# preamp.net
KiCad netlist of a schematic drawn in Altium Designer
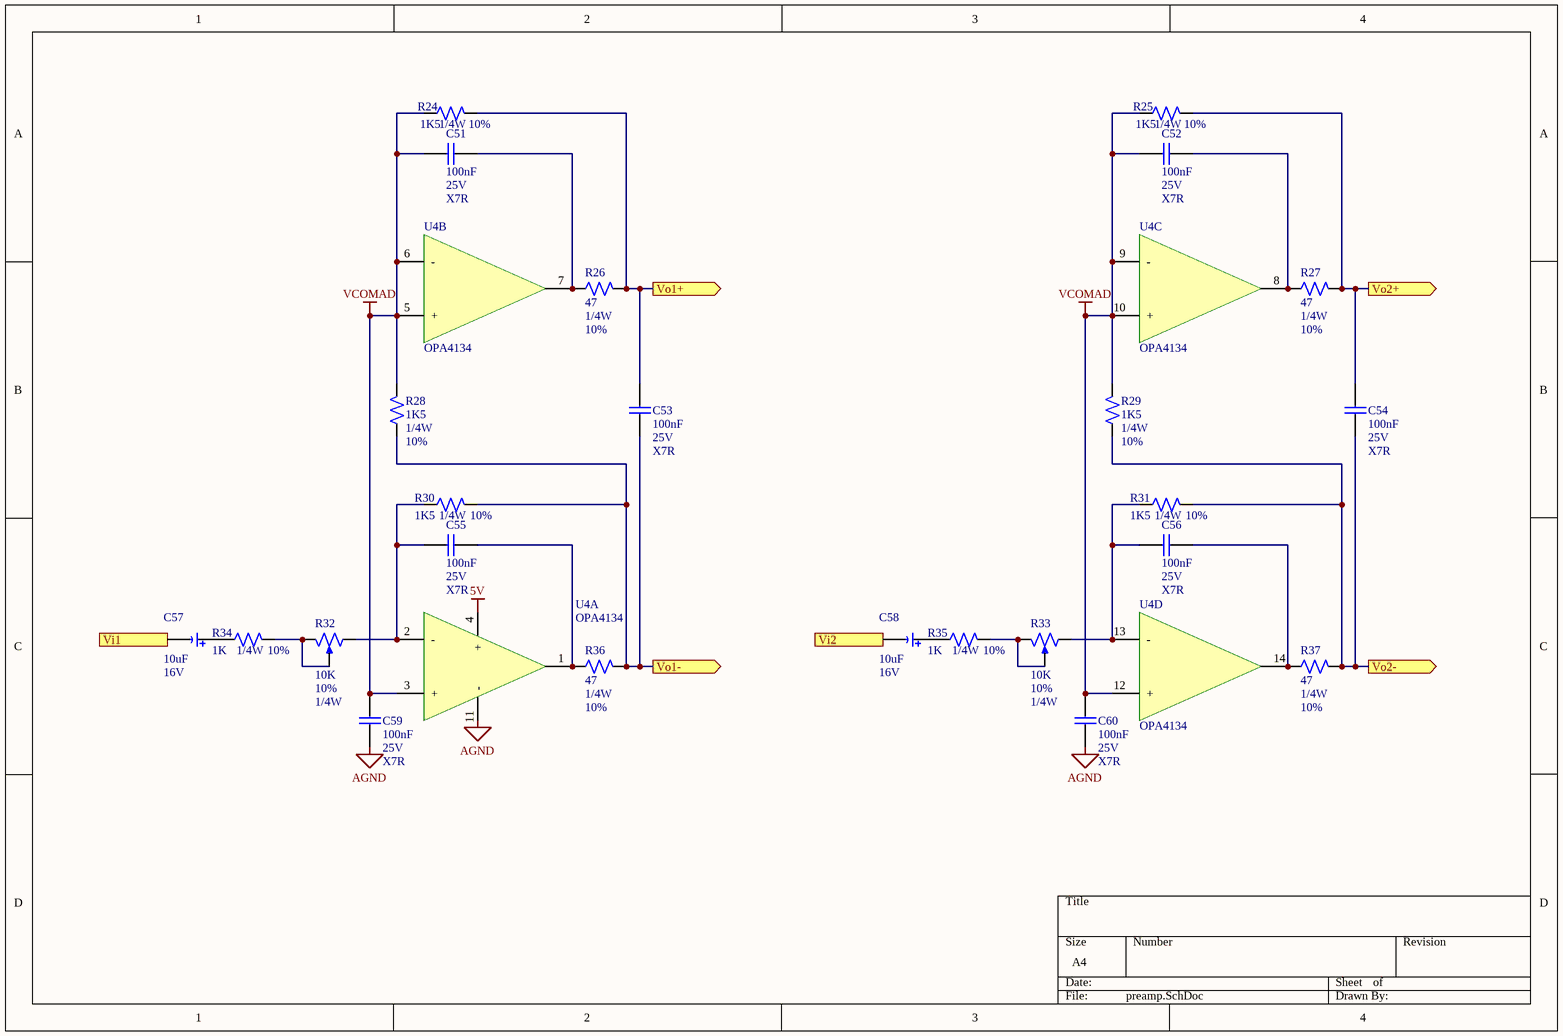
[diagram p0: preamp.SchDoc]

(export (version "E")
  (design (tool "Eeschema 10.0.6"))
  (components
    (comp (ref "C51")
      (value "Capacitor")
      (footprint "C0805")
      (description "Capacitor de placas paralelas")
      (fields (field (name "VALOR") "100nF") (field (name "TENSION") "25V") (field (name "TOLERANCIA") "X7R"))
      (libsource (lib "Sch_Comunes") (part "Capacitor"))
    )
    (comp (ref "C52")
      (value "Capacitor")
      (footprint "C0805")
      (description "Capacitor de placas paralelas")
      (fields (field (name "VALOR") "100nF") (field (name "TENSION") "25V") (field (name "TOLERANCIA") "X7R"))
      (libsource (lib "Sch_Comunes") (part "Capacitor"))
    )
    (comp (ref "C53")
      (value "Capacitor")
      (footprint "C0805")
      (description "Capacitor de placas paralelas")
      (fields (field (name "VALOR") "100nF") (field (name "TENSION") "25V") (field (name "TOLERANCIA") "X7R"))
      (libsource (lib "Sch_Comunes") (part "Capacitor"))
    )
    (comp (ref "C54")
      (value "Capacitor")
      (footprint "C0805")
      (description "Capacitor de placas paralelas")
      (fields (field (name "VALOR") "100nF") (field (name "TENSION") "25V") (field (name "TOLERANCIA") "X7R"))
      (libsource (lib "Sch_Comunes") (part "Capacitor"))
    )
    (comp (ref "C55")
      (value "Capacitor")
      (footprint "C0805")
      (description "Capacitor de placas paralelas")
      (fields (field (name "VALOR") "100nF") (field (name "TENSION") "25V") (field (name "TOLERANCIA") "X7R"))
      (libsource (lib "Sch_Comunes") (part "Capacitor"))
    )
    (comp (ref "C56")
      (value "Capacitor")
      (footprint "C0805")
      (description "Capacitor de placas paralelas")
      (fields (field (name "VALOR") "100nF") (field (name "TENSION") "25V") (field (name "TOLERANCIA") "X7R"))
      (libsource (lib "Sch_Comunes") (part "Capacitor"))
    )
    (comp (ref "C57")
      (value "Capacitor polarizado")
      (footprint "CAP_Electrolytic")
      (fields (field (name "VALOR") "10uF") (field (name "TENSION") "16V"))
      (libsource (lib "sch_comunes") (part "Capacitor polarizado"))
    )
    (comp (ref "C58")
      (value "Capacitor polarizado")
      (footprint "CAP_Electrolytic")
      (fields (field (name "VALOR") "10uF") (field (name "TENSION") "16V"))
      (libsource (lib "sch_comunes") (part "Capacitor polarizado"))
    )
    (comp (ref "C59")
      (value "Capacitor")
      (footprint "C0805")
      (description "Capacitor de placas paralelas")
      (fields (field (name "VALOR") "100nF") (field (name "TENSION") "25V") (field (name "TOLERANCIA") "X7R"))
      (libsource (lib "Sch_Comunes") (part "Capacitor"))
    )
    (comp (ref "C60")
      (value "Capacitor")
      (footprint "C0805")
      (description "Capacitor de placas paralelas")
      (fields (field (name "VALOR") "100nF") (field (name "TENSION") "25V") (field (name "TOLERANCIA") "X7R"))
      (libsource (lib "Sch_Comunes") (part "Capacitor"))
    )
    (comp (ref "R24")
      (value "Resistor")
      (footprint "R0805")
      (description "Resistencia")
      (fields (field (name "VALOR") "1K5") (field (name "POTENCIA") "1/4W") (field (name "TOLERANCIA") "10%"))
      (libsource (lib "sch_comunes") (part "Resistor"))
    )
    (comp (ref "R25")
      (value "Resistor")
      (footprint "R0805")
      (description "Resistencia")
      (fields (field (name "VALOR") "1K5") (field (name "POTENCIA") "1/4W") (field (name "TOLERANCIA") "10%"))
      (libsource (lib "sch_comunes") (part "Resistor"))
    )
    (comp (ref "R26")
      (value "Resistor")
      (footprint "R0805")
      (description "Resistencia")
      (fields (field (name "VALOR") "47") (field (name "POTENCIA") "1/4W") (field (name "TOLERANCIA") "10%"))
      (libsource (lib "sch_comunes") (part "Resistor"))
    )
    (comp (ref "R27")
      (value "Resistor")
      (footprint "R0805")
      (description "Resistencia")
      (fields (field (name "VALOR") "47") (field (name "POTENCIA") "1/4W") (field (name "TOLERANCIA") "10%"))
      (libsource (lib "sch_comunes") (part "Resistor"))
    )
    (comp (ref "R28")
      (value "Resistor")
      (footprint "R0805")
      (description "Resistencia")
      (fields (field (name "VALOR") "1K5") (field (name "POTENCIA") "1/4W") (field (name "TOLERANCIA") "10%"))
      (libsource (lib "sch_comunes") (part "Resistor"))
    )
    (comp (ref "R29")
      (value "Resistor")
      (footprint "R0805")
      (description "Resistencia")
      (fields (field (name "VALOR") "1K5") (field (name "POTENCIA") "1/4W") (field (name "TOLERANCIA") "10%"))
      (libsource (lib "sch_comunes") (part "Resistor"))
    )
    (comp (ref "R30")
      (value "Resistor")
      (footprint "R0805")
      (description "Resistencia")
      (fields (field (name "VALOR") "1K5") (field (name "POTENCIA") "1/4W") (field (name "TOLERANCIA") "10%"))
      (libsource (lib "sch_comunes") (part "Resistor"))
    )
    (comp (ref "R31")
      (value "Resistor")
      (footprint "R0805")
      (description "Resistencia")
      (fields (field (name "VALOR") "1K5") (field (name "POTENCIA") "1/4W") (field (name "TOLERANCIA") "10%"))
      (libsource (lib "sch_comunes") (part "Resistor"))
    )
    (comp (ref "R32")
      (value "Potenciometro")
      (footprint "Header 3x1")
      (fields (field (name "VALOR") "10K") (field (name "TOLERANCIA") "10%") (field (name "POTENCIA") "1/4W"))
      (libsource (lib "sch_comunes") (part "Potenciometer"))
    )
    (comp (ref "R33")
      (value "Potenciometro")
      (footprint "Header 3x1")
      (fields (field (name "VALOR") "10K") (field (name "TOLERANCIA") "10%") (field (name "POTENCIA") "1/4W"))
      (libsource (lib "sch_comunes") (part "Potenciometer"))
    )
    (comp (ref "R34")
      (value "Resistor")
      (footprint "R0805")
      (description "Resistencia")
      (fields (field (name "VALOR") "1K") (field (name "POTENCIA") "1/4W") (field (name "TOLERANCIA") "10%"))
      (libsource (lib "sch_comunes") (part "Resistor"))
    )
    (comp (ref "R35")
      (value "Resistor")
      (footprint "R0805")
      (description "Resistencia")
      (fields (field (name "VALOR") "1K") (field (name "POTENCIA") "1/4W") (field (name "TOLERANCIA") "10%"))
      (libsource (lib "sch_comunes") (part "Resistor"))
    )
    (comp (ref "R36")
      (value "Resistor")
      (footprint "R0805")
      (description "Resistencia")
      (fields (field (name "VALOR") "47") (field (name "POTENCIA") "1/4W") (field (name "TOLERANCIA") "10%"))
      (libsource (lib "sch_comunes") (part "Resistor"))
    )
    (comp (ref "R37")
      (value "Resistor")
      (footprint "R0805")
      (description "Resistencia")
      (fields (field (name "VALOR") "47") (field (name "POTENCIA") "1/4W") (field (name "TOLERANCIA") "10%"))
      (libsource (lib "sch_comunes") (part "Resistor"))
    )
    (comp (ref "U4")
      (value "OPA4134")
      (footprint "TSSOP-14")
      (description "Integrado con 4 operacionales")
      (libsource (lib "sch_opamp") (part "Opamp_x4"))
    )
  )
  (nets
    (net (code "1") (name "/Vi1") (class "Default")
      (node (ref "C57") (pin "2") (pinfunction "2_2") (pintype "passive"))
    )
    (net (code "2") (name "/Vi2") (class "Default")
      (node (ref "C58") (pin "2") (pinfunction "2_2") (pintype "passive"))
    )
    (net (code "3") (name "/Vo1+") (class "Default")
      (node (ref "C53") (pin "1") (pinfunction "1_1") (pintype "passive"))
      (node (ref "R24") (pin "2") (pinfunction "2_2") (pintype "passive"))
      (node (ref "R26") (pin "2") (pinfunction "2_2") (pintype "passive"))
    )
    (net (code "4") (name "/Vo1-") (class "Default")
      (node (ref "C53") (pin "2") (pinfunction "2_2") (pintype "passive"))
      (node (ref "R28") (pin "1") (pinfunction "1_1") (pintype "passive"))
      (node (ref "R30") (pin "2") (pinfunction "2_2") (pintype "passive"))
      (node (ref "R36") (pin "2") (pinfunction "2_2") (pintype "passive"))
    )
    (net (code "5") (name "/Vo2+") (class "Default")
      (node (ref "C54") (pin "1") (pinfunction "1_1") (pintype "passive"))
      (node (ref "R25") (pin "2") (pinfunction "2_2") (pintype "passive"))
      (node (ref "R27") (pin "2") (pinfunction "2_2") (pintype "passive"))
    )
    (net (code "6") (name "/Vo2-") (class "Default")
      (node (ref "C54") (pin "2") (pinfunction "2_2") (pintype "passive"))
      (node (ref "R29") (pin "1") (pinfunction "1_1") (pintype "passive"))
      (node (ref "R31") (pin "2") (pinfunction "2_2") (pintype "passive"))
      (node (ref "R37") (pin "2") (pinfunction "2_2") (pintype "passive"))
    )
    (net (code "7") (name "5V") (class "Default")
      (node (ref "U4") (pin "4") (pinfunction "+_4") (pintype "power_in"))
    )
    (net (code "8") (name "AGND") (class "Default")
      (node (ref "C59") (pin "2") (pinfunction "2_2") (pintype "passive"))
      (node (ref "C60") (pin "2") (pinfunction "2_2") (pintype "passive"))
      (node (ref "U4") (pin "11") (pinfunction "-_11") (pintype "passive"))
    )
    (net (code "9") (name "Net-(C57-Pad1)") (class "Default")
      (node (ref "C57") (pin "1") (pinfunction "1_1") (pintype "passive"))
      (node (ref "R34") (pin "1") (pinfunction "1_1") (pintype "passive"))
    )
    (net (code "10") (name "Net-(C58-Pad1)") (class "Default")
      (node (ref "C58") (pin "1") (pinfunction "1_1") (pintype "passive"))
      (node (ref "R35") (pin "1") (pinfunction "1_1") (pintype "passive"))
    )
    (net (code "11") (name "Net-(R32-Left)") (class "Default")
      (node (ref "R32") (pin "1") (pinfunction "Left_1") (pintype "passive"))
      (node (ref "R32") (pin "2") (pinfunction "Punto_medio_2") (pintype "passive"))
      (node (ref "R34") (pin "2") (pinfunction "2_2") (pintype "passive"))
    )
    (net (code "12") (name "Net-(R32-Right)") (class "Default")
      (node (ref "C55") (pin "2") (pinfunction "2_2") (pintype "passive"))
      (node (ref "R30") (pin "1") (pinfunction "1_1") (pintype "passive"))
      (node (ref "R32") (pin "3") (pinfunction "Right_3") (pintype "passive"))
      (node (ref "U4") (pin "2") (pinfunction "-_2") (pintype "passive"))
    )
    (net (code "13") (name "Net-(R33-Left)") (class "Default")
      (node (ref "R33") (pin "1") (pinfunction "Left_1") (pintype "passive"))
      (node (ref "R33") (pin "2") (pinfunction "Punto_medio_2") (pintype "passive"))
      (node (ref "R35") (pin "2") (pinfunction "2_2") (pintype "passive"))
    )
    (net (code "14") (name "Net-(R33-Right)") (class "Default")
      (node (ref "C56") (pin "2") (pinfunction "2_2") (pintype "passive"))
      (node (ref "R31") (pin "1") (pinfunction "1_1") (pintype "passive"))
      (node (ref "R33") (pin "3") (pinfunction "Right_3") (pintype "passive"))
      (node (ref "U4") (pin "13") (pinfunction "-_13") (pintype "passive"))
    )
    (net (code "15") (name "Net-(U4A-OUT)") (class "Default")
      (node (ref "C55") (pin "1") (pinfunction "1_1") (pintype "passive"))
      (node (ref "R36") (pin "1") (pinfunction "1_1") (pintype "passive"))
      (node (ref "U4") (pin "1") (pinfunction "OUT_1") (pintype "passive"))
    )
    (net (code "16") (name "Net-(U4B-OUT)") (class "Default")
      (node (ref "C51") (pin "1") (pinfunction "1_1") (pintype "passive"))
      (node (ref "R26") (pin "1") (pinfunction "1_1") (pintype "passive"))
      (node (ref "U4") (pin "7") (pinfunction "OUT_7") (pintype "passive"))
    )
    (net (code "17") (name "Net-(U4C-OUT)") (class "Default")
      (node (ref "C52") (pin "1") (pinfunction "1_1") (pintype "passive"))
      (node (ref "R27") (pin "1") (pinfunction "1_1") (pintype "passive"))
      (node (ref "U4") (pin "8") (pinfunction "OUT_8") (pintype "passive"))
    )
    (net (code "18") (name "Net-(U4D-OUT)") (class "Default")
      (node (ref "C56") (pin "1") (pinfunction "1_1") (pintype "passive"))
      (node (ref "R37") (pin "1") (pinfunction "1_1") (pintype "passive"))
      (node (ref "U4") (pin "14") (pinfunction "OUT_14") (pintype "passive"))
    )
    (net (code "19") (name "VCOMAD") (class "Default")
      (node (ref "C51") (pin "2") (pinfunction "2_2") (pintype "passive"))
      (node (ref "C52") (pin "2") (pinfunction "2_2") (pintype "passive"))
      (node (ref "C59") (pin "1") (pinfunction "1_1") (pintype "passive"))
      (node (ref "C60") (pin "1") (pinfunction "1_1") (pintype "passive"))
      (node (ref "R24") (pin "1") (pinfunction "1_1") (pintype "passive"))
      (node (ref "R25") (pin "1") (pinfunction "1_1") (pintype "passive"))
      (node (ref "R28") (pin "2") (pinfunction "2_2") (pintype "passive"))
      (node (ref "R29") (pin "2") (pinfunction "2_2") (pintype "passive"))
      (node (ref "U4") (pin "10") (pinfunction "+_10") (pintype "passive"))
      (node (ref "U4") (pin "12") (pinfunction "+_12") (pintype "passive"))
      (node (ref "U4") (pin "3") (pinfunction "+_3") (pintype "passive"))
      (node (ref "U4") (pin "5") (pinfunction "+_5") (pintype "passive"))
      (node (ref "U4") (pin "6") (pinfunction "-_6") (pintype "passive"))
      (node (ref "U4") (pin "9") (pinfunction "-_9") (pintype "passive"))
    )
  )
)
